# DS18B20Modular1.net
KiCad netlist of a schematic drawn in EAGLE
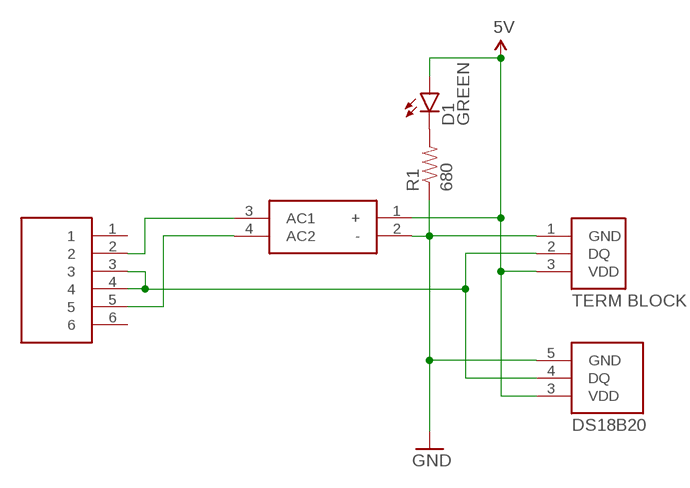
[diagram p0: schematic, sheet 1]

(export (version "E")
  (design (tool "Eeschema 10.0.6"))
  (components
    (comp (ref "D1")
      (value "GREEN")
      (footprint "eagle-import:LED-0603")
      (libsource (lib "eagle-import") (part "LED-GREEN0603"))
    )
    (comp (ref "J1")
      (value "MODULAR-JACK-6P6C-1")
      (footprint "eagle-import:MODULAR-JACK-6P6C-1")
      (libsource (lib "eagle-import") (part "MODULAR-JACK-6P6C-1"))
    )
    (comp (ref "R1")
      (value "680")
      (footprint "eagle-import:0805")
      (libsource (lib "eagle-import") (part "RES-680-0805"))
    )
    (comp (ref "U$1")
      (value "RECTIFIER-MB1S")
      (footprint "eagle-import:4-SOIC-FAIRCHILD")
      (libsource (lib "eagle-import") (part "RECTIFIER-MB1S"))
    )
    (comp (ref "U$2")
      (value "TERMBLOCK-1WIRE")
      (footprint "eagle-import:TERMBLOCK-1WIRE")
      (libsource (lib "eagle-import") (part "TERMBLOCK-1WIRE"))
    )
    (comp (ref "U$3")
      (value "DS18B208-SOIC")
      (footprint "eagle-import:DS18B20-S0")
      (libsource (lib "eagle-import") (part "DS18B208-SOIC"))
    )
  )
  (nets
    (net (code "1") (name "5V") (class "Default")
      (node (ref "D1") (pin "A") (pinfunction "A_A") (pintype "passive"))
      (node (ref "U$1") (pin "1") (pinfunction "+_1") (pintype "power_in"))
      (node (ref "U$2") (pin "3") (pinfunction "VDD_3") (pintype "power_in"))
      (node (ref "U$3") (pin "3") (pinfunction "VDD_3") (pintype "power_in"))
    )
    (net (code "2") (name "GND") (class "Default")
      (node (ref "R1") (pin "1") (pinfunction "1_1") (pintype "passive"))
      (node (ref "U$1") (pin "2") (pinfunction "-_2") (pintype "power_in"))
      (node (ref "U$2") (pin "1") (pinfunction "GND_1") (pintype "power_in"))
      (node (ref "U$3") (pin "5") (pinfunction "GND_5") (pintype "power_in"))
    )
    (net (code "3") (name "Net-(D1-PadC)") (class "Default")
      (node (ref "D1") (pin "C") (pinfunction "C_C") (pintype "passive"))
      (node (ref "R1") (pin "2") (pinfunction "2_2") (pintype "passive"))
    )
    (net (code "4") (name "Net-(U$1-AC1)") (class "Default")
      (node (ref "J1") (pin "2") (pinfunction "2_2") (pintype "passive"))
      (node (ref "U$1") (pin "3") (pinfunction "AC1_3") (pintype "passive"))
    )
    (net (code "5") (name "Net-(U$1-AC2)") (class "Default")
      (node (ref "J1") (pin "5") (pinfunction "5_5") (pintype "passive"))
      (node (ref "U$1") (pin "4") (pinfunction "AC2_4") (pintype "passive"))
    )
    (net (code "6") (name "Net-(U$2-DQ)") (class "Default")
      (node (ref "J1") (pin "3") (pinfunction "3_3") (pintype "passive"))
      (node (ref "J1") (pin "4") (pinfunction "4_4") (pintype "passive"))
      (node (ref "U$2") (pin "2") (pinfunction "DQ_2") (pintype "bidirectional"))
      (node (ref "U$3") (pin "4") (pinfunction "DQ_4") (pintype "bidirectional"))
    )
    (net (code "7") (name "unconnected-(J1-Pad1)") (class "Default")
      (node (ref "J1") (pin "1") (pinfunction "1_1") (pintype "passive"))
    )
    (net (code "8") (name "unconnected-(J1-Pad6)") (class "Default")
      (node (ref "J1") (pin "6") (pinfunction "6_6") (pintype "passive"))
    )
  )
)
